# Fri3D_Bot_2018_00.net
KiCad netlist of a schematic drawn in Altium Designer
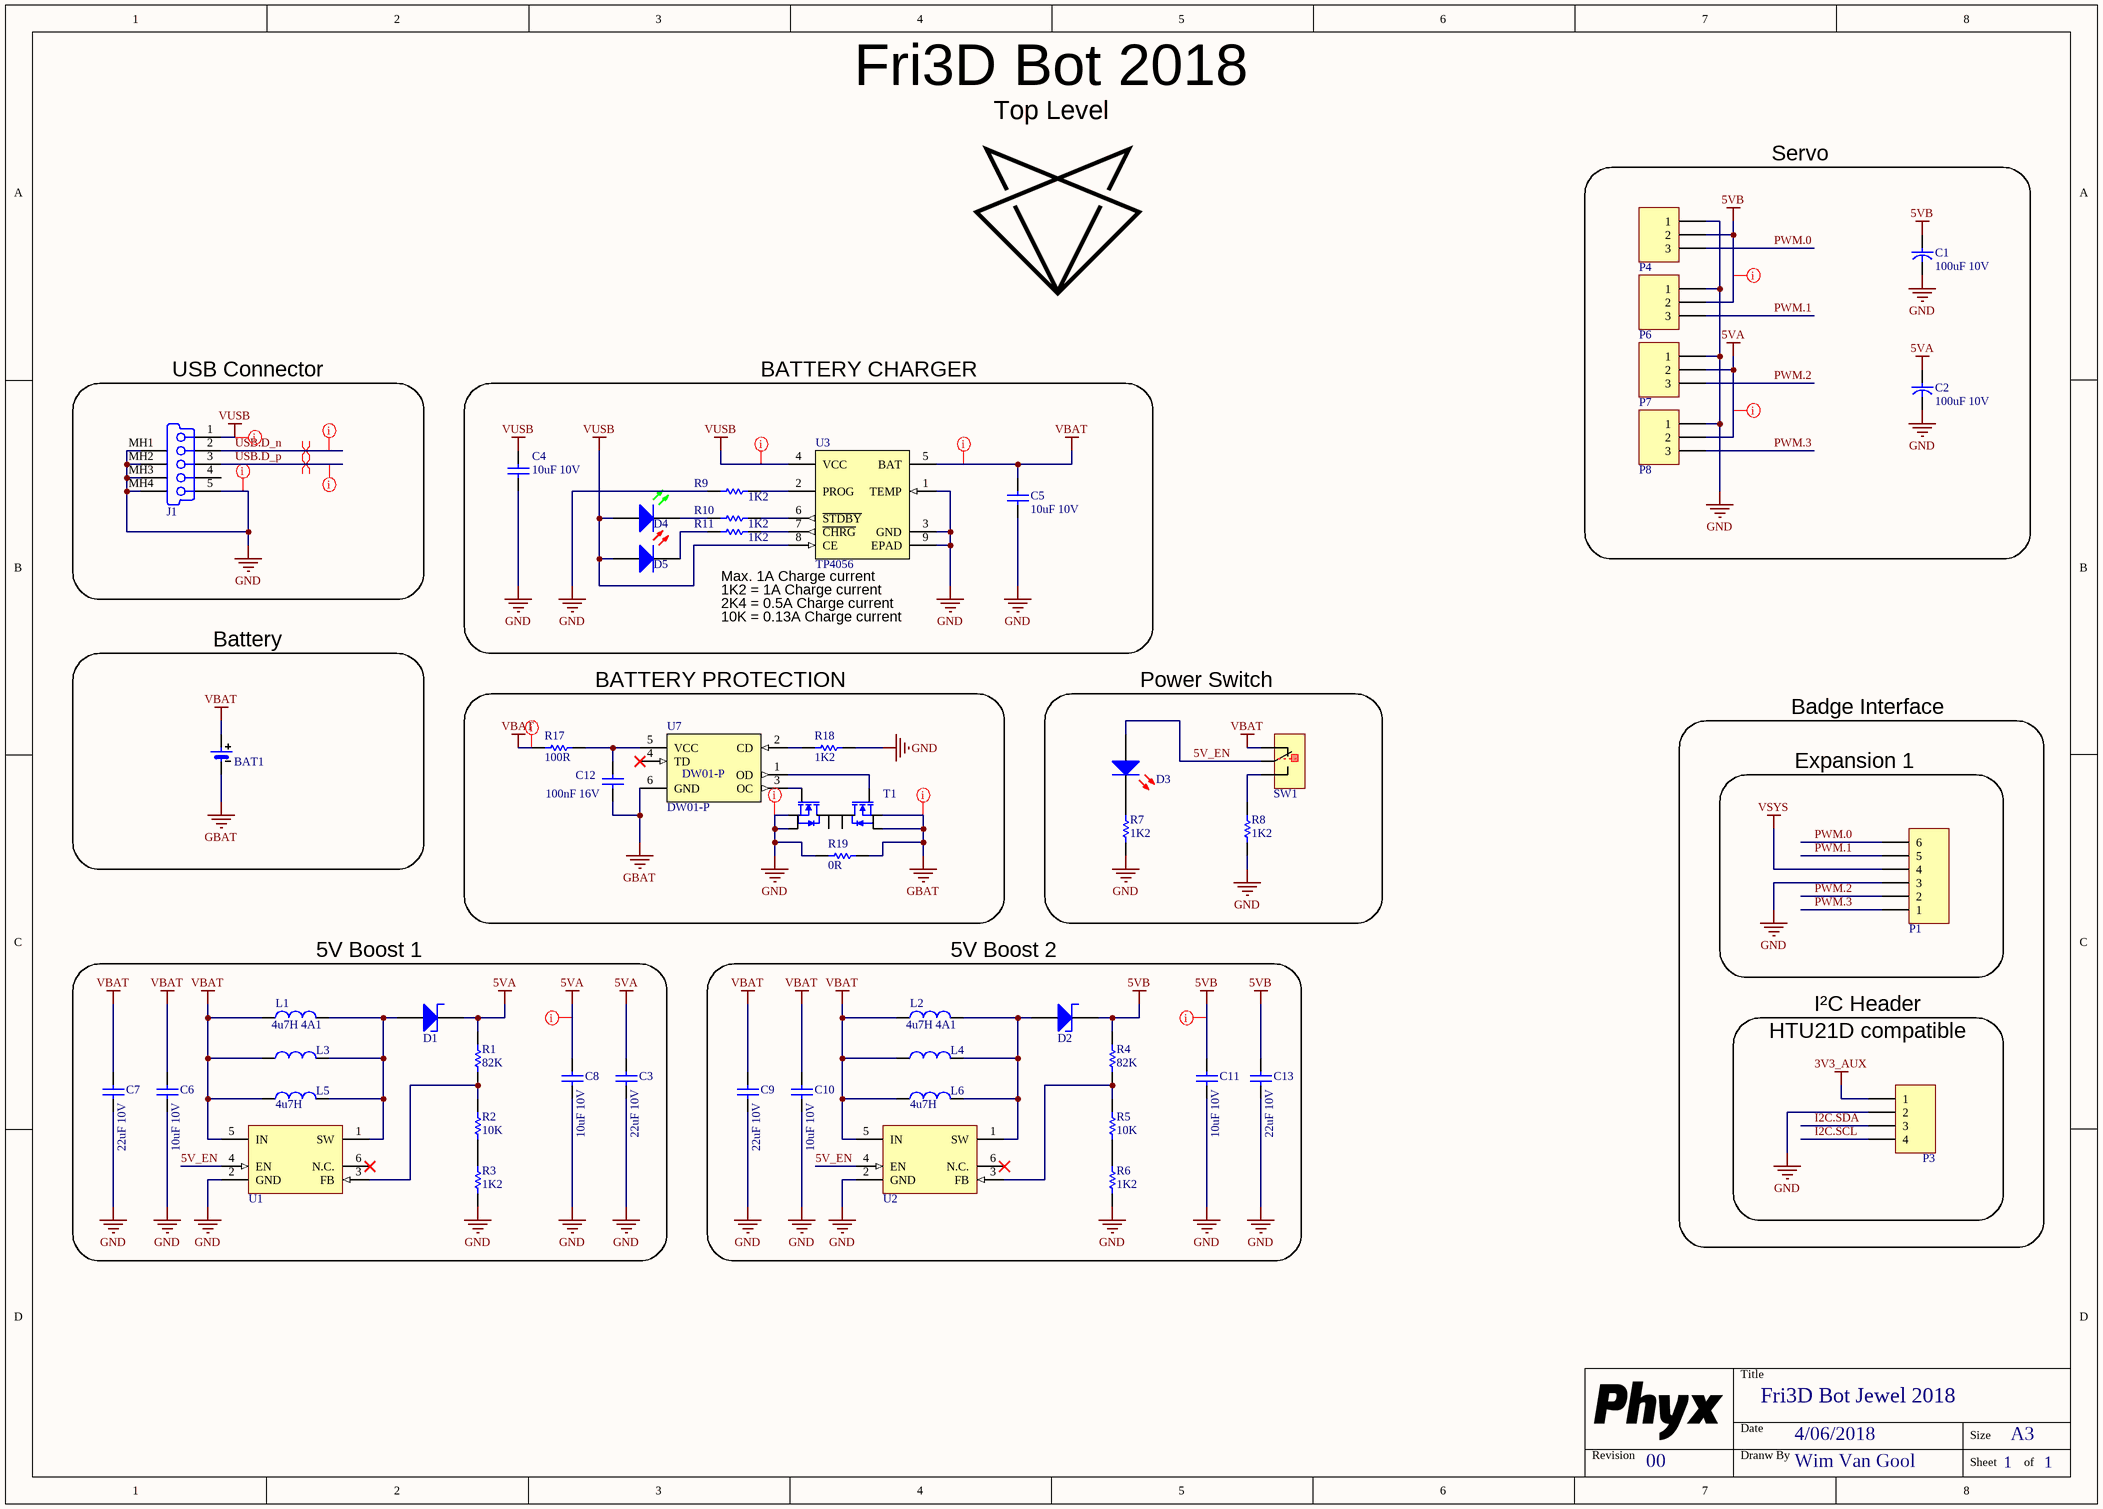
[diagram p0: Fri3D_Bot_2018_00.SchDoc]

(export (version "E")
  (design (tool "Eeschema 10.0.6"))
  (components
    (comp (ref "BAT1")
      (value "18650 Battery holder")
      (footprint "MPD_BH-18650-PC")
      (description "=Description")
      (libsource (lib "Phyx_Components") (part "BAT_2"))
    )
    (comp (ref "C1")
      (value "100uF 10V")
      (footprint "C_5x11_2mm")
      (description "Capacitor electrolyt")
      (fields (field (name "Comment") "CAP_POL"))
      (libsource (lib "Phyx_Components") (part "CAP_POL"))
    )
    (comp (ref "C2")
      (value "100uF 10V")
      (footprint "C_5x11_2mm")
      (description "Capacitor electrolyt")
      (fields (field (name "Comment") "CAP_POL"))
      (libsource (lib "Phyx_Components") (part "CAP_POL"))
    )
    (comp (ref "C3")
      (value "22uF 10V")
      (footprint "C1210_N")
      (description "Capacitor Ceramic")
      (fields (field (name "Comment") "CAP_CERAMIC"))
      (libsource (lib "Phyx_Components") (part "CAP_CERAMIC"))
    )
    (comp (ref "C4")
      (value "10uF 10V")
      (footprint "C0805_N")
      (description "Capacitor Ceramic")
      (fields (field (name "Comment") "CAP_CERAMIC"))
      (libsource (lib "Phyx_Components") (part "CAP_CERAMIC"))
    )
    (comp (ref "C5")
      (value "10uF 10V")
      (footprint "C0805_N")
      (description "Capacitor Ceramic")
      (fields (field (name "Comment") "CAP_CERAMIC"))
      (libsource (lib "Phyx_Components") (part "CAP_CERAMIC"))
    )
    (comp (ref "C6")
      (value "10uF 10V")
      (footprint "C0805_N")
      (description "Capacitor Ceramic")
      (fields (field (name "Comment") "CAP_CERAMIC"))
      (libsource (lib "Phyx_Components") (part "CAP_CERAMIC"))
    )
    (comp (ref "C7")
      (value "22uF 10V")
      (footprint "C1210_N")
      (description "Capacitor Ceramic")
      (fields (field (name "Comment") "CAP_CERAMIC"))
      (libsource (lib "Phyx_Components") (part "CAP_CERAMIC"))
    )
    (comp (ref "C8")
      (value "10uF 10V")
      (footprint "C0805_N")
      (description "Capacitor Ceramic")
      (fields (field (name "Comment") "CAP_CERAMIC"))
      (libsource (lib "Phyx_Components") (part "CAP_CERAMIC"))
    )
    (comp (ref "C9")
      (value "22uF 10V")
      (footprint "C1210_N")
      (description "Capacitor Ceramic")
      (fields (field (name "Comment") "CAP_CERAMIC"))
      (libsource (lib "Phyx_Components") (part "CAP_CERAMIC"))
    )
    (comp (ref "C10")
      (value "10uF 10V")
      (footprint "C0805_N")
      (description "Capacitor Ceramic")
      (fields (field (name "Comment") "CAP_CERAMIC"))
      (libsource (lib "Phyx_Components") (part "CAP_CERAMIC"))
    )
    (comp (ref "C11")
      (value "10uF 10V")
      (footprint "C0805_N")
      (description "Capacitor Ceramic")
      (fields (field (name "Comment") "CAP_CERAMIC"))
      (libsource (lib "Phyx_Components") (part "CAP_CERAMIC"))
    )
    (comp (ref "C12")
      (value "100nF 16V")
      (footprint "C0603_N")
      (description "Capacitor Ceramic")
      (libsource (lib "Phyx_Components") (part "CAP_CERAMIC"))
    )
    (comp (ref "C13")
      (value "22uF 10V")
      (footprint "C1210_N")
      (description "Capacitor Ceramic")
      (fields (field (name "Comment") "CAP_CERAMIC"))
      (libsource (lib "Phyx_Components") (part "CAP_CERAMIC"))
    )
    (comp (ref "D1")
      (value "TSS83L45 MWG Schottky ULTRAFAST, 3A, 45V")
      (footprint "TS_SOD128")
      (description "=Description")
      (libsource (lib "Phyx_Components") (part "Schottky_21"))
    )
    (comp (ref "D2")
      (value "TSS83L45 MWG Schottky ULTRAFAST, 3A, 45V")
      (footprint "TS_SOD128")
      (description "=Description")
      (libsource (lib "Phyx_Components") (part "Schottky_21"))
    )
    (comp (ref "D3")
      (value "Default 0805 Red LED")
      (footprint "LED_0805_RD")
      (description "=Description")
      (libsource (lib "Phyx_Components") (part "LED_RED"))
    )
    (comp (ref "D4")
      (value "Default 0805 Green LED")
      (footprint "LED_0805_GR")
      (description "=Description")
      (libsource (lib "Phyx_Components") (part "LED_GREEN"))
    )
    (comp (ref "D5")
      (value "Default 0805 Red LED")
      (footprint "LED_0805_RD")
      (description "=Description")
      (libsource (lib "Phyx_Components") (part "LED_RED"))
    )
    (comp (ref "J1")
      (value "Amphenol FCI 10118194-0001LF Micro USB 1.8A TH Lock")
      (footprint "FCI_10118194-0001LF")
      (libsource (lib "Phyx_Components") (part "USB_OTG_Mini-B"))
    )
    (comp (ref "L1")
      (value "4u7H 4A1")
      (footprint "TAI_NRS8040")
      (fields (field (name "Comment") "NRS8040T4R7NJGJ"))
      (libsource (lib "Phyx_Components") (part "INDUCTOR"))
    )
    (comp (ref "L2")
      (value "4u7H 4A1")
      (footprint "TAI_NRS8040")
      (fields (field (name "Comment") "NRS8040T4R7NJGJ"))
      (libsource (lib "Phyx_Components") (part "INDUCTOR"))
    )
    (comp (ref "L3")
      (value "VLC6045T-3R3N")
      (footprint "IND_6045")
      (libsource (lib "Phyx_Components") (part "INDUCTOR"))
    )
    (comp (ref "L4")
      (value "VLC6045T-3R3N")
      (footprint "IND_6045")
      (libsource (lib "Phyx_Components") (part "INDUCTOR"))
    )
    (comp (ref "L5")
      (value "4u7H")
      (footprint "SNL_SWPA4020")
      (fields (field (name "Comment") "SWPA4020S4R7MT"))
      (libsource (lib "Phyx_Components") (part "INDUCTOR"))
    )
    (comp (ref "L6")
      (value "4u7H")
      (footprint "SNL_SWPA4020")
      (fields (field (name "Comment") "SWPA4020S4R7MT"))
      (libsource (lib "Phyx_Components") (part "INDUCTOR"))
    )
    (comp (ref "P1")
      (value "Header 6")
      (footprint "HDR1X6")
      (libsource (lib "Phyx_Components") (part "Header 6"))
    )
    (comp (ref "P3")
      (value "Header 4")
      (footprint "HDR1X4")
      (libsource (lib "Phyx_Components") (part "Header 4"))
    )
    (comp (ref "P4")
      (value "Header 3")
      (footprint "HDR1X3")
      (libsource (lib "Phyx_Components") (part "Header 3"))
    )
    (comp (ref "P6")
      (value "Header 3")
      (footprint "HDR1X3")
      (libsource (lib "Phyx_Components") (part "Header 3"))
    )
    (comp (ref "P7")
      (value "Header 3")
      (footprint "HDR1X3")
      (libsource (lib "Phyx_Components") (part "Header 3"))
    )
    (comp (ref "P8")
      (value "Header 3")
      (footprint "HDR1X3")
      (libsource (lib "Phyx_Components") (part "Header 3"))
    )
    (comp (ref "R1")
      (value "82K")
      (footprint "R0603_N")
      (fields (field (name "Comment") "RESISTOR"))
      (libsource (lib "Phyx_Components") (part "RESISTOR"))
    )
    (comp (ref "R2")
      (value "10K")
      (footprint "R0603_N")
      (fields (field (name "Comment") "RESISTOR"))
      (libsource (lib "Phyx_Components") (part "RESISTOR"))
    )
    (comp (ref "R3")
      (value "1K2")
      (footprint "R0603_N")
      (fields (field (name "Comment") "RESISTOR"))
      (libsource (lib "Phyx_Components") (part "RESISTOR"))
    )
    (comp (ref "R4")
      (value "82K")
      (footprint "R0603_N")
      (fields (field (name "Comment") "RESISTOR"))
      (libsource (lib "Phyx_Components") (part "RESISTOR"))
    )
    (comp (ref "R5")
      (value "10K")
      (footprint "R0603_N")
      (fields (field (name "Comment") "RESISTOR"))
      (libsource (lib "Phyx_Components") (part "RESISTOR"))
    )
    (comp (ref "R6")
      (value "1K2")
      (footprint "R0603_N")
      (fields (field (name "Comment") "RESISTOR"))
      (libsource (lib "Phyx_Components") (part "RESISTOR"))
    )
    (comp (ref "R7")
      (value "1K2")
      (footprint "R0603_N")
      (fields (field (name "Comment") "RESISTOR"))
      (libsource (lib "Phyx_Components") (part "RESISTOR"))
    )
    (comp (ref "R8")
      (value "1K2")
      (footprint "R0603_N")
      (fields (field (name "Comment") "RESISTOR"))
      (libsource (lib "Phyx_Components") (part "RESISTOR"))
    )
    (comp (ref "R9")
      (value "1K2")
      (footprint "R0603_N")
      (fields (field (name "Comment") "RESISTOR"))
      (libsource (lib "Phyx_Components") (part "RESISTOR"))
    )
    (comp (ref "R10")
      (value "1K2")
      (footprint "R0603_N")
      (fields (field (name "Comment") "RESISTOR"))
      (libsource (lib "Phyx_Components") (part "RESISTOR"))
    )
    (comp (ref "R11")
      (value "1K2")
      (footprint "R0603_N")
      (fields (field (name "Comment") "RESISTOR"))
      (libsource (lib "Phyx_Components") (part "RESISTOR"))
    )
    (comp (ref "R17")
      (value "100R")
      (footprint "R0603_N")
      (fields (field (name "Comment") "RESISTOR"))
      (libsource (lib "Phyx_Components") (part "RESISTOR"))
    )
    (comp (ref "R18")
      (value "1K2")
      (footprint "R0603_N")
      (fields (field (name "Comment") "RESISTOR"))
      (libsource (lib "Phyx_Components") (part "RESISTOR"))
    )
    (comp (ref "R19")
      (value "0R")
      (footprint "R1206")
      (fields (field (name "Comment") "RESISTOR"))
      (libsource (lib "Phyx_Components") (part "RESISTOR"))
    )
    (comp (ref "SW1")
      (value "mini Switch 1 pole double throw right angle")
      (footprint "SK-12D07")
      (libsource (lib "Phyx_Components") (part "SW_1P2T"))
    )
    (comp (ref "T1")
      (value "Dual N-Ch MOSFET Common Drain")
      (footprint "TSSOP_8_65P")
      (description "=Description")
      (libsource (lib "Phyx_Components") (part "N_MOSFET_FS8205A"))
    )
    (comp (ref "U1")
      (value "High Efficiency 1.2MHz 2A Step Up Converter  SX1308")
      (footprint "SOT23-6")
      (description "=Description")
      (libsource (lib "Phyx_Components") (part "SX1308_Boost"))
    )
    (comp (ref "U2")
      (value "High Efficiency 1.2MHz 2A Step Up Converter  SX1308")
      (footprint "SOT23-6")
      (description "=Description")
      (libsource (lib "Phyx_Components") (part "SX1308_Boost"))
    )
    (comp (ref "U3")
      (value "TP4056")
      (footprint "SOIC_N_8_TH")
      (description "=Description")
      (fields (field (name "Comment") "Single Cell LiIon charger max 1A"))
      (libsource (lib "Phyx_Components") (part "TP4056"))
    )
    (comp (ref "U7")
      (value "DW01-P")
      (footprint "SOT23-6")
      (description "=Description")
      (fields (field (name "Comment") "DW01-P single cell lithium protection"))
      (libsource (lib "Phyx_Components") (part "DW01-P"))
    )
  )
  (nets
    (net (code "1") (name "/5V_EN") (class "Default")
      (node (ref "D3") (pin "1") (pinfunction "A_1") (pintype "passive"))
      (node (ref "SW1") (pin "2") (pinfunction "2_2") (pintype "passive"))
      (node (ref "U1") (pin "4") (pinfunction "EN_4") (pintype "input"))
      (node (ref "U2") (pin "4") (pinfunction "EN_4") (pintype "input"))
    )
    (net (code "2") (name "/I2C.SCL") (class "Default")
      (node (ref "P3") (pin "4") (pinfunction "4_4") (pintype "passive"))
    )
    (net (code "3") (name "/I2C.SDA") (class "Default")
      (node (ref "P3") (pin "3") (pinfunction "3_3") (pintype "passive"))
    )
    (net (code "4") (name "/PWM.0") (class "Default")
      (node (ref "P1") (pin "6") (pinfunction "6_6") (pintype "passive"))
      (node (ref "P4") (pin "3") (pinfunction "3_3") (pintype "passive"))
    )
    (net (code "5") (name "/PWM.1") (class "Default")
      (node (ref "P1") (pin "5") (pinfunction "5_5") (pintype "passive"))
      (node (ref "P6") (pin "3") (pinfunction "3_3") (pintype "passive"))
    )
    (net (code "6") (name "/PWM.2") (class "Default")
      (node (ref "P1") (pin "2") (pinfunction "2_2") (pintype "passive"))
      (node (ref "P7") (pin "3") (pinfunction "3_3") (pintype "passive"))
    )
    (net (code "7") (name "/PWM.3") (class "Default")
      (node (ref "P1") (pin "1") (pinfunction "1_1") (pintype "passive"))
      (node (ref "P8") (pin "3") (pinfunction "3_3") (pintype "passive"))
    )
    (net (code "8") (name "/USB.D_n") (class "Default")
      (node (ref "J1") (pin "2") (pinfunction "D-_2") (pintype "passive"))
    )
    (net (code "9") (name "/USB.D_p") (class "Default")
      (node (ref "J1") (pin "3") (pinfunction "D+_3") (pintype "passive"))
    )
    (net (code "10") (name "3V3_AUX") (class "Default")
      (node (ref "P3") (pin "1") (pinfunction "1_1") (pintype "passive"))
    )
    (net (code "11") (name "5VA") (class "Default")
      (node (ref "C2") (pin "1") (pinfunction "1_1") (pintype "passive"))
      (node (ref "C3") (pin "1") (pinfunction "1_1") (pintype "passive"))
      (node (ref "C8") (pin "1") (pinfunction "1_1") (pintype "passive"))
      (node (ref "D1") (pin "1") (pinfunction "C_1") (pintype "passive"))
      (node (ref "P7") (pin "2") (pinfunction "2_2") (pintype "passive"))
      (node (ref "P8") (pin "2") (pinfunction "2_2") (pintype "passive"))
      (node (ref "R1") (pin "1") (pinfunction "1_1") (pintype "passive"))
    )
    (net (code "12") (name "5VB") (class "Default")
      (node (ref "C1") (pin "1") (pinfunction "1_1") (pintype "passive"))
      (node (ref "C11") (pin "1") (pinfunction "1_1") (pintype "passive"))
      (node (ref "C13") (pin "1") (pinfunction "1_1") (pintype "passive"))
      (node (ref "D2") (pin "1") (pinfunction "C_1") (pintype "passive"))
      (node (ref "P4") (pin "2") (pinfunction "2_2") (pintype "passive"))
      (node (ref "P6") (pin "2") (pinfunction "2_2") (pintype "passive"))
      (node (ref "R4") (pin "1") (pinfunction "1_1") (pintype "passive"))
    )
    (net (code "13") (name "GBAT") (class "Default")
      (node (ref "BAT1") (pin "2") (pinfunction "2_2") (pintype "passive"))
      (node (ref "C12") (pin "2") (pinfunction "2_2") (pintype "passive"))
      (node (ref "R19") (pin "1") (pinfunction "1_1") (pintype "passive"))
      (node (ref "T1") (pin "2") (pinfunction "S1_2") (pintype "passive"))
      (node (ref "T1") (pin "3") (pinfunction "S1_3") (pintype "passive"))
      (node (ref "U7") (pin "6") (pinfunction "GND_6") (pintype "power_in"))
    )
    (net (code "14") (name "GND") (class "Default")
      (node (ref "C1") (pin "2") (pinfunction "2_2") (pintype "passive"))
      (node (ref "C10") (pin "2") (pinfunction "2_2") (pintype "passive"))
      (node (ref "C11") (pin "2") (pinfunction "2_2") (pintype "passive"))
      (node (ref "C13") (pin "2") (pinfunction "2_2") (pintype "passive"))
      (node (ref "C2") (pin "2") (pinfunction "2_2") (pintype "passive"))
      (node (ref "C3") (pin "2") (pinfunction "2_2") (pintype "passive"))
      (node (ref "C4") (pin "2") (pinfunction "2_2") (pintype "passive"))
      (node (ref "C5") (pin "2") (pinfunction "2_2") (pintype "passive"))
      (node (ref "C6") (pin "2") (pinfunction "2_2") (pintype "passive"))
      (node (ref "C7") (pin "2") (pinfunction "2_2") (pintype "passive"))
      (node (ref "C8") (pin "2") (pinfunction "2_2") (pintype "passive"))
      (node (ref "C9") (pin "2") (pinfunction "2_2") (pintype "passive"))
      (node (ref "J1") (pin "5") (pinfunction "GND_5") (pintype "passive"))
      (node (ref "J1") (pin "MH1") (pinfunction "Tab_MH1") (pintype "passive"))
      (node (ref "J1") (pin "MH2") (pinfunction "Tab_MH2") (pintype "passive"))
      (node (ref "J1") (pin "MH3") (pinfunction "Tab_MH3") (pintype "passive"))
      (node (ref "J1") (pin "MH4") (pinfunction "Tab_MH4") (pintype "passive"))
      (node (ref "P1") (pin "3") (pinfunction "3_3") (pintype "passive"))
      (node (ref "P3") (pin "2") (pinfunction "2_2") (pintype "passive"))
      (node (ref "P4") (pin "1") (pinfunction "1_1") (pintype "passive"))
      (node (ref "P6") (pin "1") (pinfunction "1_1") (pintype "passive"))
      (node (ref "P7") (pin "1") (pinfunction "1_1") (pintype "passive"))
      (node (ref "P8") (pin "1") (pinfunction "1_1") (pintype "passive"))
      (node (ref "R18") (pin "2") (pinfunction "2_2") (pintype "passive"))
      (node (ref "R19") (pin "2") (pinfunction "2_2") (pintype "passive"))
      (node (ref "R3") (pin "2") (pinfunction "2_2") (pintype "passive"))
      (node (ref "R6") (pin "2") (pinfunction "2_2") (pintype "passive"))
      (node (ref "R7") (pin "2") (pinfunction "2_2") (pintype "passive"))
      (node (ref "R8") (pin "2") (pinfunction "2_2") (pintype "passive"))
      (node (ref "R9") (pin "2") (pinfunction "2_2") (pintype "passive"))
      (node (ref "T1") (pin "6") (pinfunction "S2_6") (pintype "passive"))
      (node (ref "T1") (pin "7") (pinfunction "S2_7") (pintype "passive"))
      (node (ref "U1") (pin "2") (pinfunction "GND_2") (pintype "power_in"))
      (node (ref "U2") (pin "2") (pinfunction "GND_2") (pintype "power_in"))
      (node (ref "U3") (pin "1") (pinfunction "TEMP_1") (pintype "input"))
      (node (ref "U3") (pin "3") (pinfunction "GND_3") (pintype "power_in"))
      (node (ref "U3") (pin "9") (pinfunction "EPAD_9") (pintype "power_in"))
    )
    (net (code "15") (name "Net-(D1-A)") (class "Default")
      (node (ref "D1") (pin "2") (pinfunction "A_2") (pintype "passive"))
      (node (ref "L1") (pin "2") (pinfunction "2_2") (pintype "passive"))
      (node (ref "L3") (pin "2") (pinfunction "2_2") (pintype "passive"))
      (node (ref "L5") (pin "2") (pinfunction "2_2") (pintype "passive"))
      (node (ref "U1") (pin "1") (pinfunction "SW_1") (pintype "power_in"))
    )
    (net (code "16") (name "Net-(D2-A)") (class "Default")
      (node (ref "D2") (pin "2") (pinfunction "A_2") (pintype "passive"))
      (node (ref "L2") (pin "2") (pinfunction "2_2") (pintype "passive"))
      (node (ref "L4") (pin "2") (pinfunction "2_2") (pintype "passive"))
      (node (ref "L6") (pin "2") (pinfunction "2_2") (pintype "passive"))
      (node (ref "U2") (pin "1") (pinfunction "SW_1") (pintype "power_in"))
    )
    (net (code "17") (name "Net-(D3-K)") (class "Default")
      (node (ref "D3") (pin "2") (pinfunction "K_2") (pintype "passive"))
      (node (ref "R7") (pin "1") (pinfunction "1_1") (pintype "passive"))
    )
    (net (code "18") (name "Net-(D4-K)") (class "Default")
      (node (ref "D4") (pin "2") (pinfunction "K_2") (pintype "passive"))
      (node (ref "R10") (pin "1") (pinfunction "1_1") (pintype "passive"))
    )
    (net (code "19") (name "Net-(D5-K)") (class "Default")
      (node (ref "D5") (pin "2") (pinfunction "K_2") (pintype "passive"))
      (node (ref "R11") (pin "1") (pinfunction "1_1") (pintype "passive"))
    )
    (net (code "20") (name "Net-(R2-Pad2)") (class "Default")
      (node (ref "R2") (pin "2") (pinfunction "2_2") (pintype "passive"))
      (node (ref "R3") (pin "1") (pinfunction "1_1") (pintype "passive"))
    )
    (net (code "21") (name "Net-(R5-Pad2)") (class "Default")
      (node (ref "R5") (pin "2") (pinfunction "2_2") (pintype "passive"))
      (node (ref "R6") (pin "1") (pinfunction "1_1") (pintype "passive"))
    )
    (net (code "22") (name "Net-(R8-Pad1)") (class "Default")
      (node (ref "R8") (pin "1") (pinfunction "1_1") (pintype "passive"))
      (node (ref "SW1") (pin "3") (pinfunction "3_3") (pintype "passive"))
    )
    (net (code "23") (name "Net-(T1-G1)") (class "Default")
      (node (ref "T1") (pin "4") (pinfunction "G1_4") (pintype "passive"))
      (node (ref "U7") (pin "1") (pinfunction "OD_1") (pintype "output"))
    )
    (net (code "24") (name "Net-(T1-G2)") (class "Default")
      (node (ref "T1") (pin "5") (pinfunction "G2_5") (pintype "passive"))
      (node (ref "U7") (pin "3") (pinfunction "OC_3") (pintype "output"))
    )
    (net (code "25") (name "Net-(U1-FB)") (class "Default")
      (node (ref "R1") (pin "2") (pinfunction "2_2") (pintype "passive"))
      (node (ref "R2") (pin "1") (pinfunction "1_1") (pintype "passive"))
      (node (ref "U1") (pin "3") (pinfunction "FB_3") (pintype "input"))
    )
    (net (code "26") (name "Net-(U2-FB)") (class "Default")
      (node (ref "R4") (pin "2") (pinfunction "2_2") (pintype "passive"))
      (node (ref "R5") (pin "1") (pinfunction "1_1") (pintype "passive"))
      (node (ref "U2") (pin "3") (pinfunction "FB_3") (pintype "input"))
    )
    (net (code "27") (name "Net-(U3-PROG)") (class "Default")
      (node (ref "R9") (pin "1") (pinfunction "1_1") (pintype "passive"))
      (node (ref "U3") (pin "2") (pinfunction "PROG_2") (pintype "passive"))
    )
    (net (code "28") (name "Net-(U3-~{CHRG})") (class "Default")
      (node (ref "R11") (pin "2") (pinfunction "2_2") (pintype "passive"))
      (node (ref "U3") (pin "7") (pinfunction "~{CHRG}_7") (pintype "output"))
    )
    (net (code "29") (name "Net-(U3-~{STDBY})") (class "Default")
      (node (ref "R10") (pin "2") (pinfunction "2_2") (pintype "passive"))
      (node (ref "U3") (pin "6") (pinfunction "~{STDBY}_6") (pintype "output"))
    )
    (net (code "30") (name "Net-(U7-CD)") (class "Default")
      (node (ref "R18") (pin "1") (pinfunction "1_1") (pintype "passive"))
      (node (ref "U7") (pin "2") (pinfunction "CD_2") (pintype "input"))
    )
    (net (code "31") (name "Net-(U7-VCC)") (class "Default")
      (node (ref "C12") (pin "1") (pinfunction "1_1") (pintype "passive"))
      (node (ref "R17") (pin "2") (pinfunction "2_2") (pintype "passive"))
      (node (ref "U7") (pin "5") (pinfunction "VCC_5") (pintype "power_in"))
    )
    (net (code "32") (name "VBAT") (class "Default")
      (node (ref "BAT1") (pin "1") (pinfunction "1_1") (pintype "passive"))
      (node (ref "C10") (pin "1") (pinfunction "1_1") (pintype "passive"))
      (node (ref "C5") (pin "1") (pinfunction "1_1") (pintype "passive"))
      (node (ref "C6") (pin "1") (pinfunction "1_1") (pintype "passive"))
      (node (ref "C7") (pin "1") (pinfunction "1_1") (pintype "passive"))
      (node (ref "C9") (pin "1") (pinfunction "1_1") (pintype "passive"))
      (node (ref "L1") (pin "1") (pinfunction "1_1") (pintype "passive"))
      (node (ref "L2") (pin "1") (pinfunction "1_1") (pintype "passive"))
      (node (ref "L3") (pin "1") (pinfunction "1_1") (pintype "passive"))
      (node (ref "L4") (pin "1") (pinfunction "1_1") (pintype "passive"))
      (node (ref "L5") (pin "1") (pinfunction "1_1") (pintype "passive"))
      (node (ref "L6") (pin "1") (pinfunction "1_1") (pintype "passive"))
      (node (ref "R17") (pin "1") (pinfunction "1_1") (pintype "passive"))
      (node (ref "SW1") (pin "1") (pinfunction "1_1") (pintype "passive"))
      (node (ref "U1") (pin "5") (pinfunction "IN_5") (pintype "power_in"))
      (node (ref "U2") (pin "5") (pinfunction "IN_5") (pintype "power_in"))
      (node (ref "U3") (pin "5") (pinfunction "BAT_5") (pintype "power_in"))
    )
    (net (code "33") (name "VSYS") (class "Default")
      (node (ref "P1") (pin "4") (pinfunction "4_4") (pintype "passive"))
    )
    (net (code "34") (name "VUSB") (class "Default")
      (node (ref "C4") (pin "1") (pinfunction "1_1") (pintype "passive"))
      (node (ref "D4") (pin "1") (pinfunction "A_1") (pintype "passive"))
      (node (ref "D5") (pin "1") (pinfunction "A_1") (pintype "passive"))
      (node (ref "J1") (pin "1") (pinfunction "V_BUS_(5V)_1") (pintype "passive"))
      (node (ref "U3") (pin "4") (pinfunction "VCC_4") (pintype "power_in"))
      (node (ref "U3") (pin "8") (pinfunction "CE_8") (pintype "input"))
    )
    (net (code "35") (name "unconnected-(J1-NC-Pad4)") (class "Default")
      (node (ref "J1") (pin "4") (pinfunction "NC_4") (pintype "passive"))
    )
    (net (code "36") (name "unconnected-(T1-D1-Pad1)") (class "Default")
      (node (ref "T1") (pin "1") (pinfunction "D1_1") (pintype "passive"))
    )
    (net (code "37") (name "unconnected-(T1-D2-Pad8)") (class "Default")
      (node (ref "T1") (pin "8") (pinfunction "D2_8") (pintype "passive"))
    )
    (net (code "38") (name "unconnected-(U1-N.C.-Pad6)") (class "Default")
      (node (ref "U1") (pin "6") (pinfunction "N.C._6") (pintype "power_in+no_connect"))
    )
    (net (code "39") (name "unconnected-(U2-N.C.-Pad6)") (class "Default")
      (node (ref "U2") (pin "6") (pinfunction "N.C._6") (pintype "power_in+no_connect"))
    )
    (net (code "40") (name "unconnected-(U7-TD-Pad4)") (class "Default")
      (node (ref "U7") (pin "4") (pinfunction "TD_4") (pintype "input+no_connect"))
    )
  )
)
